# MegaShield.net
KiCad netlist of a schematic drawn in EAGLE
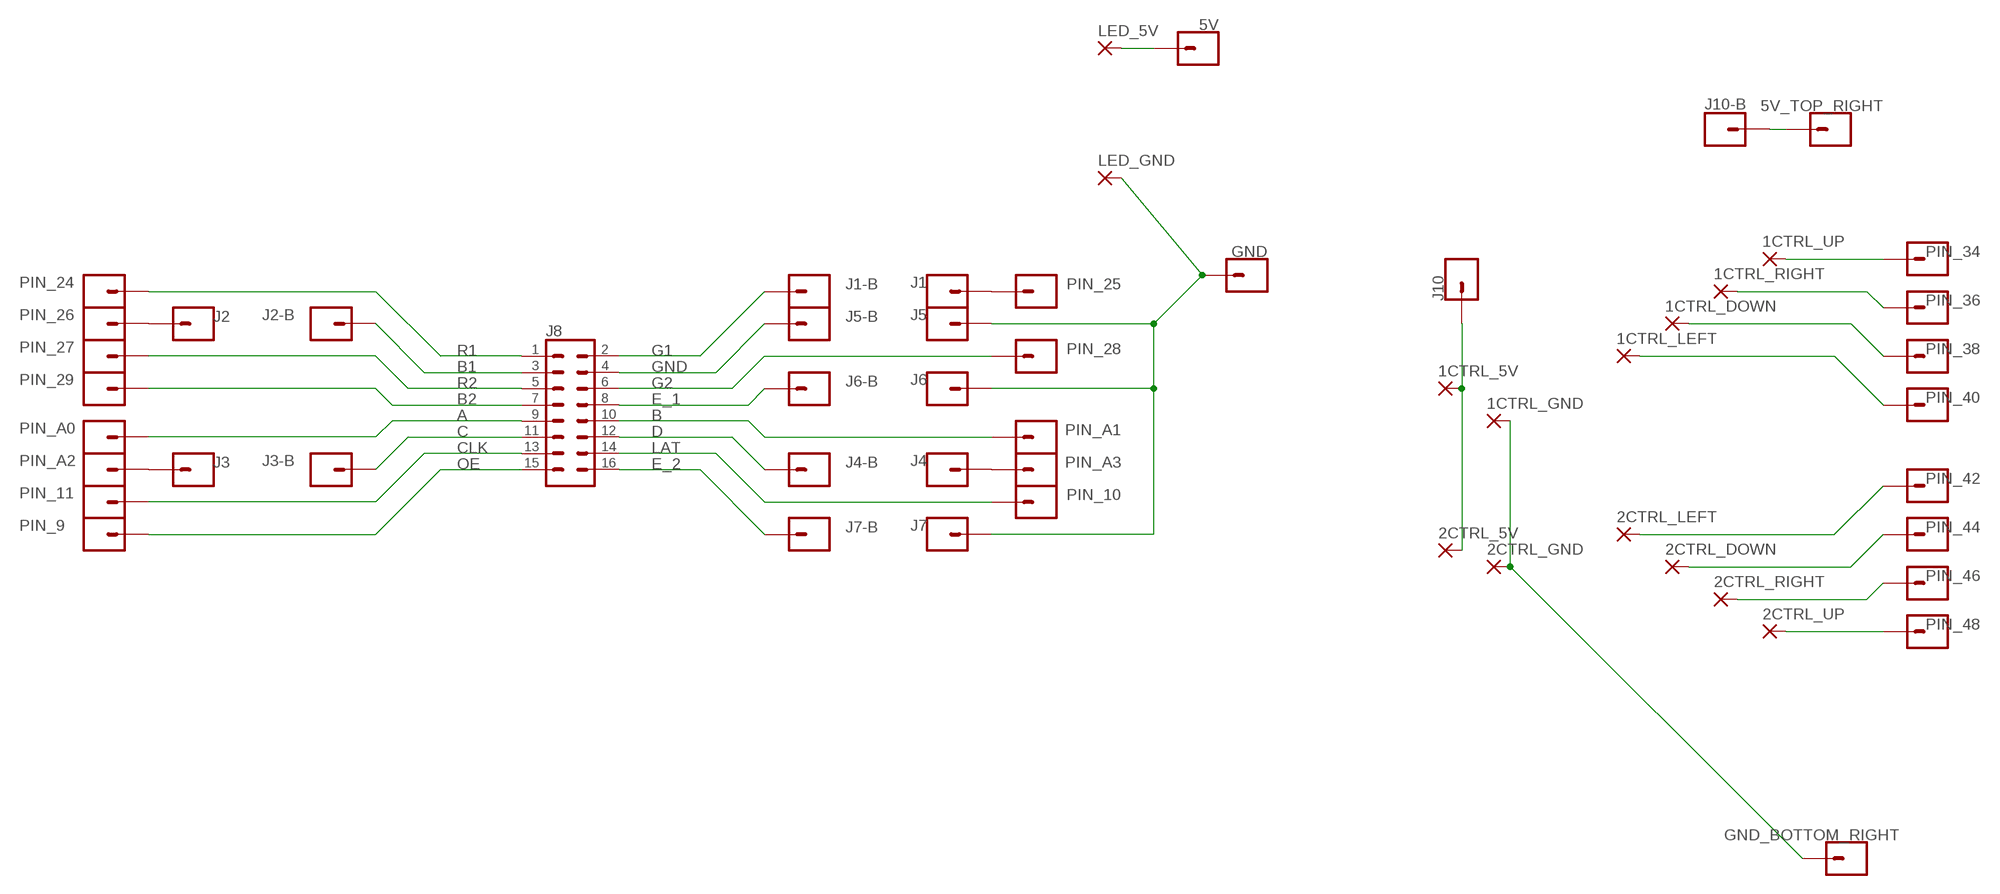
[diagram p0: schematic, sheet 1]

(export (version "E")
  (design (tool "Eeschema 10.0.6"))
  (components
    (comp (ref "1CTRL_5V")
      (value "PADSMALL")
      (footprint "eagle-import:SMD2,54-5,08")
      (libsource (lib "eagle-import") (part "PADSMALL"))
    )
    (comp (ref "1CTRL_DOWN")
      (value "PADSMALL")
      (footprint "eagle-import:SMD2,54-5,08")
      (libsource (lib "eagle-import") (part "PADSMALL"))
    )
    (comp (ref "1CTRL_GND")
      (value "PADSMALL")
      (footprint "eagle-import:SMD2,54-5,08")
      (libsource (lib "eagle-import") (part "PADSMALL"))
    )
    (comp (ref "1CTRL_LEFT")
      (value "PADSMALL")
      (footprint "eagle-import:SMD2,54-5,08")
      (libsource (lib "eagle-import") (part "PADSMALL"))
    )
    (comp (ref "1CTRL_RIGHT")
      (value "PADSMALL")
      (footprint "eagle-import:SMD2,54-5,08")
      (libsource (lib "eagle-import") (part "PADSMALL"))
    )
    (comp (ref "1CTRL_UP")
      (value "PADSMALL")
      (footprint "eagle-import:SMD2,54-5,08")
      (libsource (lib "eagle-import") (part "PADSMALL"))
    )
    (comp (ref "2CTRL_5V")
      (value "PADSMALL")
      (footprint "eagle-import:SMD2,54-5,08")
      (libsource (lib "eagle-import") (part "PADSMALL"))
    )
    (comp (ref "2CTRL_DOWN")
      (value "PADSMALL")
      (footprint "eagle-import:SMD2,54-5,08")
      (libsource (lib "eagle-import") (part "PADSMALL"))
    )
    (comp (ref "2CTRL_GND")
      (value "PADSMALL")
      (footprint "eagle-import:SMD2,54-5,08")
      (libsource (lib "eagle-import") (part "PADSMALL"))
    )
    (comp (ref "2CTRL_LEFT")
      (value "PADSMALL")
      (footprint "eagle-import:SMD2,54-5,08")
      (libsource (lib "eagle-import") (part "PADSMALL"))
    )
    (comp (ref "2CTRL_RIGHT")
      (value "PADSMALL")
      (footprint "eagle-import:SMD2,54-5,08")
      (libsource (lib "eagle-import") (part "PADSMALL"))
    )
    (comp (ref "2CTRL_UP")
      (value "PADSMALL")
      (footprint "eagle-import:SMD2,54-5,08")
      (libsource (lib "eagle-import") (part "PADSMALL"))
    )
    (comp (ref "5V")
      (value "CONN_01")
      (footprint "eagle-import:1X01")
      (libsource (lib "eagle-import") (part "CONN_01"))
    )
    (comp (ref "5V_TOP_RIGHT")
      (value "CONN_01")
      (footprint "eagle-import:1X01")
      (libsource (lib "eagle-import") (part "SparkFun-Connectors_CONN_01"))
    )
    (comp (ref "GND")
      (value "CONN_01")
      (footprint "eagle-import:1X01")
      (libsource (lib "eagle-import") (part "CONN_01"))
    )
    (comp (ref "GND_BOTTOM_RIGHT")
      (value "CONN_01")
      (footprint "eagle-import:1X01")
      (libsource (lib "eagle-import") (part "SparkFun-Connectors_CONN_01"))
    )
    (comp (ref "J1")
      (value "CONN_01")
      (footprint "eagle-import:1X01")
      (libsource (lib "eagle-import") (part "SparkFun-Connectors_CONN_01"))
    )
    (comp (ref "J1-B")
      (value "CONN_01")
      (footprint "eagle-import:1X01")
      (libsource (lib "eagle-import") (part "SparkFun-Connectors_CONN_01"))
    )
    (comp (ref "J2")
      (value "CONN_01")
      (footprint "eagle-import:1X01")
      (libsource (lib "eagle-import") (part "SparkFun-Connectors_CONN_01"))
    )
    (comp (ref "J2-B")
      (value "CONN_01")
      (footprint "eagle-import:1X01")
      (libsource (lib "eagle-import") (part "SparkFun-Connectors_CONN_01"))
    )
    (comp (ref "J3")
      (value "CONN_01")
      (footprint "eagle-import:1X01")
      (libsource (lib "eagle-import") (part "SparkFun-Connectors_CONN_01"))
    )
    (comp (ref "J3-B")
      (value "CONN_01")
      (footprint "eagle-import:1X01")
      (libsource (lib "eagle-import") (part "SparkFun-Connectors_CONN_01"))
    )
    (comp (ref "J4")
      (value "CONN_01")
      (footprint "eagle-import:1X01")
      (libsource (lib "eagle-import") (part "SparkFun-Connectors_CONN_01"))
    )
    (comp (ref "J4-B")
      (value "CONN_01")
      (footprint "eagle-import:1X01")
      (libsource (lib "eagle-import") (part "SparkFun-Connectors_CONN_01"))
    )
    (comp (ref "J5")
      (value "CONN_01")
      (footprint "eagle-import:1X01")
      (libsource (lib "eagle-import") (part "SparkFun-Connectors_CONN_01"))
    )
    (comp (ref "J5-B")
      (value "CONN_01")
      (footprint "eagle-import:1X01")
      (libsource (lib "eagle-import") (part "SparkFun-Connectors_CONN_01"))
    )
    (comp (ref "J6")
      (value "CONN_01")
      (footprint "eagle-import:1X01")
      (libsource (lib "eagle-import") (part "SparkFun-Connectors_CONN_01"))
    )
    (comp (ref "J6-B")
      (value "CONN_01")
      (footprint "eagle-import:1X01")
      (libsource (lib "eagle-import") (part "SparkFun-Connectors_CONN_01"))
    )
    (comp (ref "J7")
      (value "CONN_01")
      (footprint "eagle-import:1X01")
      (libsource (lib "eagle-import") (part "SparkFun-Connectors_CONN_01"))
    )
    (comp (ref "J7-B")
      (value "CONN_01")
      (footprint "eagle-import:1X01")
      (libsource (lib "eagle-import") (part "SparkFun-Connectors_CONN_01"))
    )
    (comp (ref "J8")
      (value "CONN_08X2_SHROUD")
      (footprint "eagle-import:2X8-SHROUDED_LOCK")
      (libsource (lib "eagle-import") (part "CONN_08X2_SHROUD"))
    )
    (comp (ref "J10")
      (value "CONN_01")
      (footprint "eagle-import:1X01")
      (libsource (lib "eagle-import") (part "SparkFun-Connectors_CONN_01"))
    )
    (comp (ref "J10-B")
      (value "CONN_01")
      (footprint "eagle-import:1X01")
      (libsource (lib "eagle-import") (part "SparkFun-Connectors_CONN_01"))
    )
    (comp (ref "LED_5V")
      (value "PAD_EXLARGE")
      (footprint "eagle-import:SMD_EXLARGE")
      (libsource (lib "eagle-import") (part "PAD_EXLARGE"))
    )
    (comp (ref "LED_GND")
      (value "PAD_EXLARGE")
      (footprint "eagle-import:SMD_EXLARGE")
      (libsource (lib "eagle-import") (part "PAD_EXLARGE"))
    )
    (comp (ref "PIN_9")
      (value "CONN_01")
      (footprint "eagle-import:1X01")
      (libsource (lib "eagle-import") (part "CONN_01"))
    )
    (comp (ref "PIN_10")
      (value "CONN_01")
      (footprint "eagle-import:1X01")
      (libsource (lib "eagle-import") (part "CONN_01"))
    )
    (comp (ref "PIN_11")
      (value "CONN_01")
      (footprint "eagle-import:1X01")
      (libsource (lib "eagle-import") (part "CONN_01"))
    )
    (comp (ref "PIN_24")
      (value "CONN_01")
      (footprint "eagle-import:1X01")
      (libsource (lib "eagle-import") (part "CONN_01"))
    )
    (comp (ref "PIN_25")
      (value "CONN_01")
      (footprint "eagle-import:1X01")
      (libsource (lib "eagle-import") (part "CONN_01"))
    )
    (comp (ref "PIN_26")
      (value "CONN_01")
      (footprint "eagle-import:1X01")
      (libsource (lib "eagle-import") (part "CONN_01"))
    )
    (comp (ref "PIN_27")
      (value "CONN_01")
      (footprint "eagle-import:1X01")
      (libsource (lib "eagle-import") (part "CONN_01"))
    )
    (comp (ref "PIN_28")
      (value "CONN_01")
      (footprint "eagle-import:1X01")
      (libsource (lib "eagle-import") (part "CONN_01"))
    )
    (comp (ref "PIN_29")
      (value "CONN_01")
      (footprint "eagle-import:1X01")
      (libsource (lib "eagle-import") (part "CONN_01"))
    )
    (comp (ref "PIN_34")
      (value "CONN_01")
      (footprint "eagle-import:1X01")
      (libsource (lib "eagle-import") (part "CONN_01"))
    )
    (comp (ref "PIN_36")
      (value "CONN_01")
      (footprint "eagle-import:1X01")
      (libsource (lib "eagle-import") (part "CONN_01"))
    )
    (comp (ref "PIN_38")
      (value "CONN_01")
      (footprint "eagle-import:1X01")
      (libsource (lib "eagle-import") (part "CONN_01"))
    )
    (comp (ref "PIN_40")
      (value "CONN_01")
      (footprint "eagle-import:1X01")
      (libsource (lib "eagle-import") (part "CONN_01"))
    )
    (comp (ref "PIN_42")
      (value "CONN_01")
      (footprint "eagle-import:1X01")
      (libsource (lib "eagle-import") (part "CONN_01"))
    )
    (comp (ref "PIN_44")
      (value "CONN_01")
      (footprint "eagle-import:1X01")
      (libsource (lib "eagle-import") (part "CONN_01"))
    )
    (comp (ref "PIN_46")
      (value "CONN_01")
      (footprint "eagle-import:1X01")
      (libsource (lib "eagle-import") (part "CONN_01"))
    )
    (comp (ref "PIN_48")
      (value "CONN_01")
      (footprint "eagle-import:1X01")
      (libsource (lib "eagle-import") (part "CONN_01"))
    )
    (comp (ref "PIN_A0")
      (value "CONN_01")
      (footprint "eagle-import:1X01")
      (libsource (lib "eagle-import") (part "CONN_01"))
    )
    (comp (ref "PIN_A1")
      (value "CONN_01")
      (footprint "eagle-import:1X01")
      (libsource (lib "eagle-import") (part "CONN_01"))
    )
    (comp (ref "PIN_A2")
      (value "CONN_01")
      (footprint "eagle-import:1X01")
      (libsource (lib "eagle-import") (part "CONN_01"))
    )
    (comp (ref "PIN_A3")
      (value "CONN_01")
      (footprint "eagle-import:1X01")
      (libsource (lib "eagle-import") (part "CONN_01"))
    )
  )
  (nets
    (net (code "1") (name "/A") (class "Default")
      (node (ref "J8") (pin "9") (pinfunction "9_9") (pintype "passive"))
      (node (ref "PIN_A0") (pin "1") (pinfunction "1_1") (pintype "passive"))
    )
    (net (code "2") (name "/B") (class "Default")
      (node (ref "J8") (pin "10") (pinfunction "10_10") (pintype "passive"))
      (node (ref "PIN_A1") (pin "1") (pinfunction "1_1") (pintype "passive"))
    )
    (net (code "3") (name "/B1") (class "Default")
      (node (ref "J2-B") (pin "1") (pinfunction "1_1") (pintype "passive"))
      (node (ref "J8") (pin "3") (pinfunction "3_3") (pintype "passive"))
    )
    (net (code "4") (name "/B2") (class "Default")
      (node (ref "J8") (pin "7") (pinfunction "7_7") (pintype "passive"))
      (node (ref "PIN_29") (pin "1") (pinfunction "1_1") (pintype "passive"))
    )
    (net (code "5") (name "/C") (class "Default")
      (node (ref "J3-B") (pin "1") (pinfunction "1_1") (pintype "passive"))
      (node (ref "J8") (pin "11") (pinfunction "11_11") (pintype "passive"))
    )
    (net (code "6") (name "/CLK") (class "Default")
      (node (ref "J8") (pin "13") (pinfunction "13_13") (pintype "passive"))
      (node (ref "PIN_11") (pin "1") (pinfunction "1_1") (pintype "passive"))
    )
    (net (code "7") (name "/D") (class "Default")
      (node (ref "J4-B") (pin "1") (pinfunction "1_1") (pintype "passive"))
      (node (ref "J8") (pin "12") (pinfunction "12_12") (pintype "passive"))
    )
    (net (code "8") (name "/E_1") (class "Default")
      (node (ref "J6-B") (pin "1") (pinfunction "1_1") (pintype "passive"))
      (node (ref "J8") (pin "8") (pinfunction "8_8") (pintype "passive"))
    )
    (net (code "9") (name "/E_2") (class "Default")
      (node (ref "J7-B") (pin "1") (pinfunction "1_1") (pintype "passive"))
      (node (ref "J8") (pin "16") (pinfunction "16_16") (pintype "passive"))
    )
    (net (code "10") (name "/G1") (class "Default")
      (node (ref "J1-B") (pin "1") (pinfunction "1_1") (pintype "passive"))
      (node (ref "J8") (pin "2") (pinfunction "2_2") (pintype "passive"))
    )
    (net (code "11") (name "/G2") (class "Default")
      (node (ref "J8") (pin "6") (pinfunction "6_6") (pintype "passive"))
      (node (ref "PIN_28") (pin "1") (pinfunction "1_1") (pintype "passive"))
    )
    (net (code "12") (name "/GND") (class "Default")
      (node (ref "J5-B") (pin "1") (pinfunction "1_1") (pintype "passive"))
      (node (ref "J8") (pin "4") (pinfunction "4_4") (pintype "passive"))
    )
    (net (code "13") (name "/LAT") (class "Default")
      (node (ref "J8") (pin "14") (pinfunction "14_14") (pintype "passive"))
      (node (ref "PIN_10") (pin "1") (pinfunction "1_1") (pintype "passive"))
    )
    (net (code "14") (name "/OE") (class "Default")
      (node (ref "J8") (pin "15") (pinfunction "15_15") (pintype "passive"))
      (node (ref "PIN_9") (pin "1") (pinfunction "1_1") (pintype "passive"))
    )
    (net (code "15") (name "/R1") (class "Default")
      (node (ref "J8") (pin "1") (pinfunction "1_1") (pintype "passive"))
      (node (ref "PIN_24") (pin "1") (pinfunction "1_1") (pintype "passive"))
    )
    (net (code "16") (name "/R2") (class "Default")
      (node (ref "J8") (pin "5") (pinfunction "5_5") (pintype "passive"))
      (node (ref "PIN_27") (pin "1") (pinfunction "1_1") (pintype "passive"))
    )
    (net (code "17") (name "Net-(1CTRL_5V-P)") (class "Default")
      (node (ref "1CTRL_5V") (pin "1") (pinfunction "P_1") (pintype "passive"))
      (node (ref "2CTRL_5V") (pin "1") (pinfunction "P_1") (pintype "passive"))
      (node (ref "J10") (pin "1") (pinfunction "1_1") (pintype "passive"))
    )
    (net (code "18") (name "Net-(1CTRL_DOWN-P)") (class "Default")
      (node (ref "1CTRL_DOWN") (pin "1") (pinfunction "P_1") (pintype "passive"))
      (node (ref "PIN_38") (pin "1") (pinfunction "1_1") (pintype "passive"))
    )
    (net (code "19") (name "Net-(1CTRL_GND-P)") (class "Default")
      (node (ref "1CTRL_GND") (pin "1") (pinfunction "P_1") (pintype "passive"))
      (node (ref "2CTRL_GND") (pin "1") (pinfunction "P_1") (pintype "passive"))
      (node (ref "GND_BOTTOM_RIGHT") (pin "1") (pinfunction "1_1") (pintype "passive"))
    )
    (net (code "20") (name "Net-(1CTRL_LEFT-P)") (class "Default")
      (node (ref "1CTRL_LEFT") (pin "1") (pinfunction "P_1") (pintype "passive"))
      (node (ref "PIN_40") (pin "1") (pinfunction "1_1") (pintype "passive"))
    )
    (net (code "21") (name "Net-(1CTRL_RIGHT-P)") (class "Default")
      (node (ref "1CTRL_RIGHT") (pin "1") (pinfunction "P_1") (pintype "passive"))
      (node (ref "PIN_36") (pin "1") (pinfunction "1_1") (pintype "passive"))
    )
    (net (code "22") (name "Net-(1CTRL_UP-P)") (class "Default")
      (node (ref "1CTRL_UP") (pin "1") (pinfunction "P_1") (pintype "passive"))
      (node (ref "PIN_34") (pin "1") (pinfunction "1_1") (pintype "passive"))
    )
    (net (code "23") (name "Net-(2CTRL_DOWN-P)") (class "Default")
      (node (ref "2CTRL_DOWN") (pin "1") (pinfunction "P_1") (pintype "passive"))
      (node (ref "PIN_44") (pin "1") (pinfunction "1_1") (pintype "passive"))
    )
    (net (code "24") (name "Net-(2CTRL_LEFT-P)") (class "Default")
      (node (ref "2CTRL_LEFT") (pin "1") (pinfunction "P_1") (pintype "passive"))
      (node (ref "PIN_42") (pin "1") (pinfunction "1_1") (pintype "passive"))
    )
    (net (code "25") (name "Net-(2CTRL_RIGHT-P)") (class "Default")
      (node (ref "2CTRL_RIGHT") (pin "1") (pinfunction "P_1") (pintype "passive"))
      (node (ref "PIN_46") (pin "1") (pinfunction "1_1") (pintype "passive"))
    )
    (net (code "26") (name "Net-(2CTRL_UP-P)") (class "Default")
      (node (ref "2CTRL_UP") (pin "1") (pinfunction "P_1") (pintype "passive"))
      (node (ref "PIN_48") (pin "1") (pinfunction "1_1") (pintype "passive"))
    )
    (net (code "27") (name "Net-(5V_TOP_RIGHT-Pad1)") (class "Default")
      (node (ref "5V_TOP_RIGHT") (pin "1") (pinfunction "1_1") (pintype "passive"))
      (node (ref "J10-B") (pin "1") (pinfunction "1_1") (pintype "passive"))
    )
    (net (code "28") (name "Net-(J1-Pad1)") (class "Default")
      (node (ref "J1") (pin "1") (pinfunction "1_1") (pintype "passive"))
      (node (ref "PIN_25") (pin "1") (pinfunction "1_1") (pintype "passive"))
    )
    (net (code "29") (name "Net-(J2-Pad1)") (class "Default")
      (node (ref "J2") (pin "1") (pinfunction "1_1") (pintype "passive"))
      (node (ref "PIN_26") (pin "1") (pinfunction "1_1") (pintype "passive"))
    )
    (net (code "30") (name "Net-(J3-Pad1)") (class "Default")
      (node (ref "J3") (pin "1") (pinfunction "1_1") (pintype "passive"))
      (node (ref "PIN_A2") (pin "1") (pinfunction "1_1") (pintype "passive"))
    )
    (net (code "31") (name "Net-(J4-Pad1)") (class "Default")
      (node (ref "J4") (pin "1") (pinfunction "1_1") (pintype "passive"))
      (node (ref "PIN_A3") (pin "1") (pinfunction "1_1") (pintype "passive"))
    )
    (net (code "32") (name "Net-(LED_5V-P)") (class "Default")
      (node (ref "5V") (pin "1") (pinfunction "1_1") (pintype "passive"))
      (node (ref "LED_5V") (pin "P$1") (pinfunction "P_P$1") (pintype "passive"))
    )
    (net (code "33") (name "Net-(LED_GND-P)") (class "Default")
      (node (ref "GND") (pin "1") (pinfunction "1_1") (pintype "passive"))
      (node (ref "J5") (pin "1") (pinfunction "1_1") (pintype "passive"))
      (node (ref "J6") (pin "1") (pinfunction "1_1") (pintype "passive"))
      (node (ref "J7") (pin "1") (pinfunction "1_1") (pintype "passive"))
      (node (ref "LED_GND") (pin "P$1") (pinfunction "P_P$1") (pintype "passive"))
    )
  )
)
